# Sheet2.net
KiCad netlist of a schematic drawn in Altium Designer
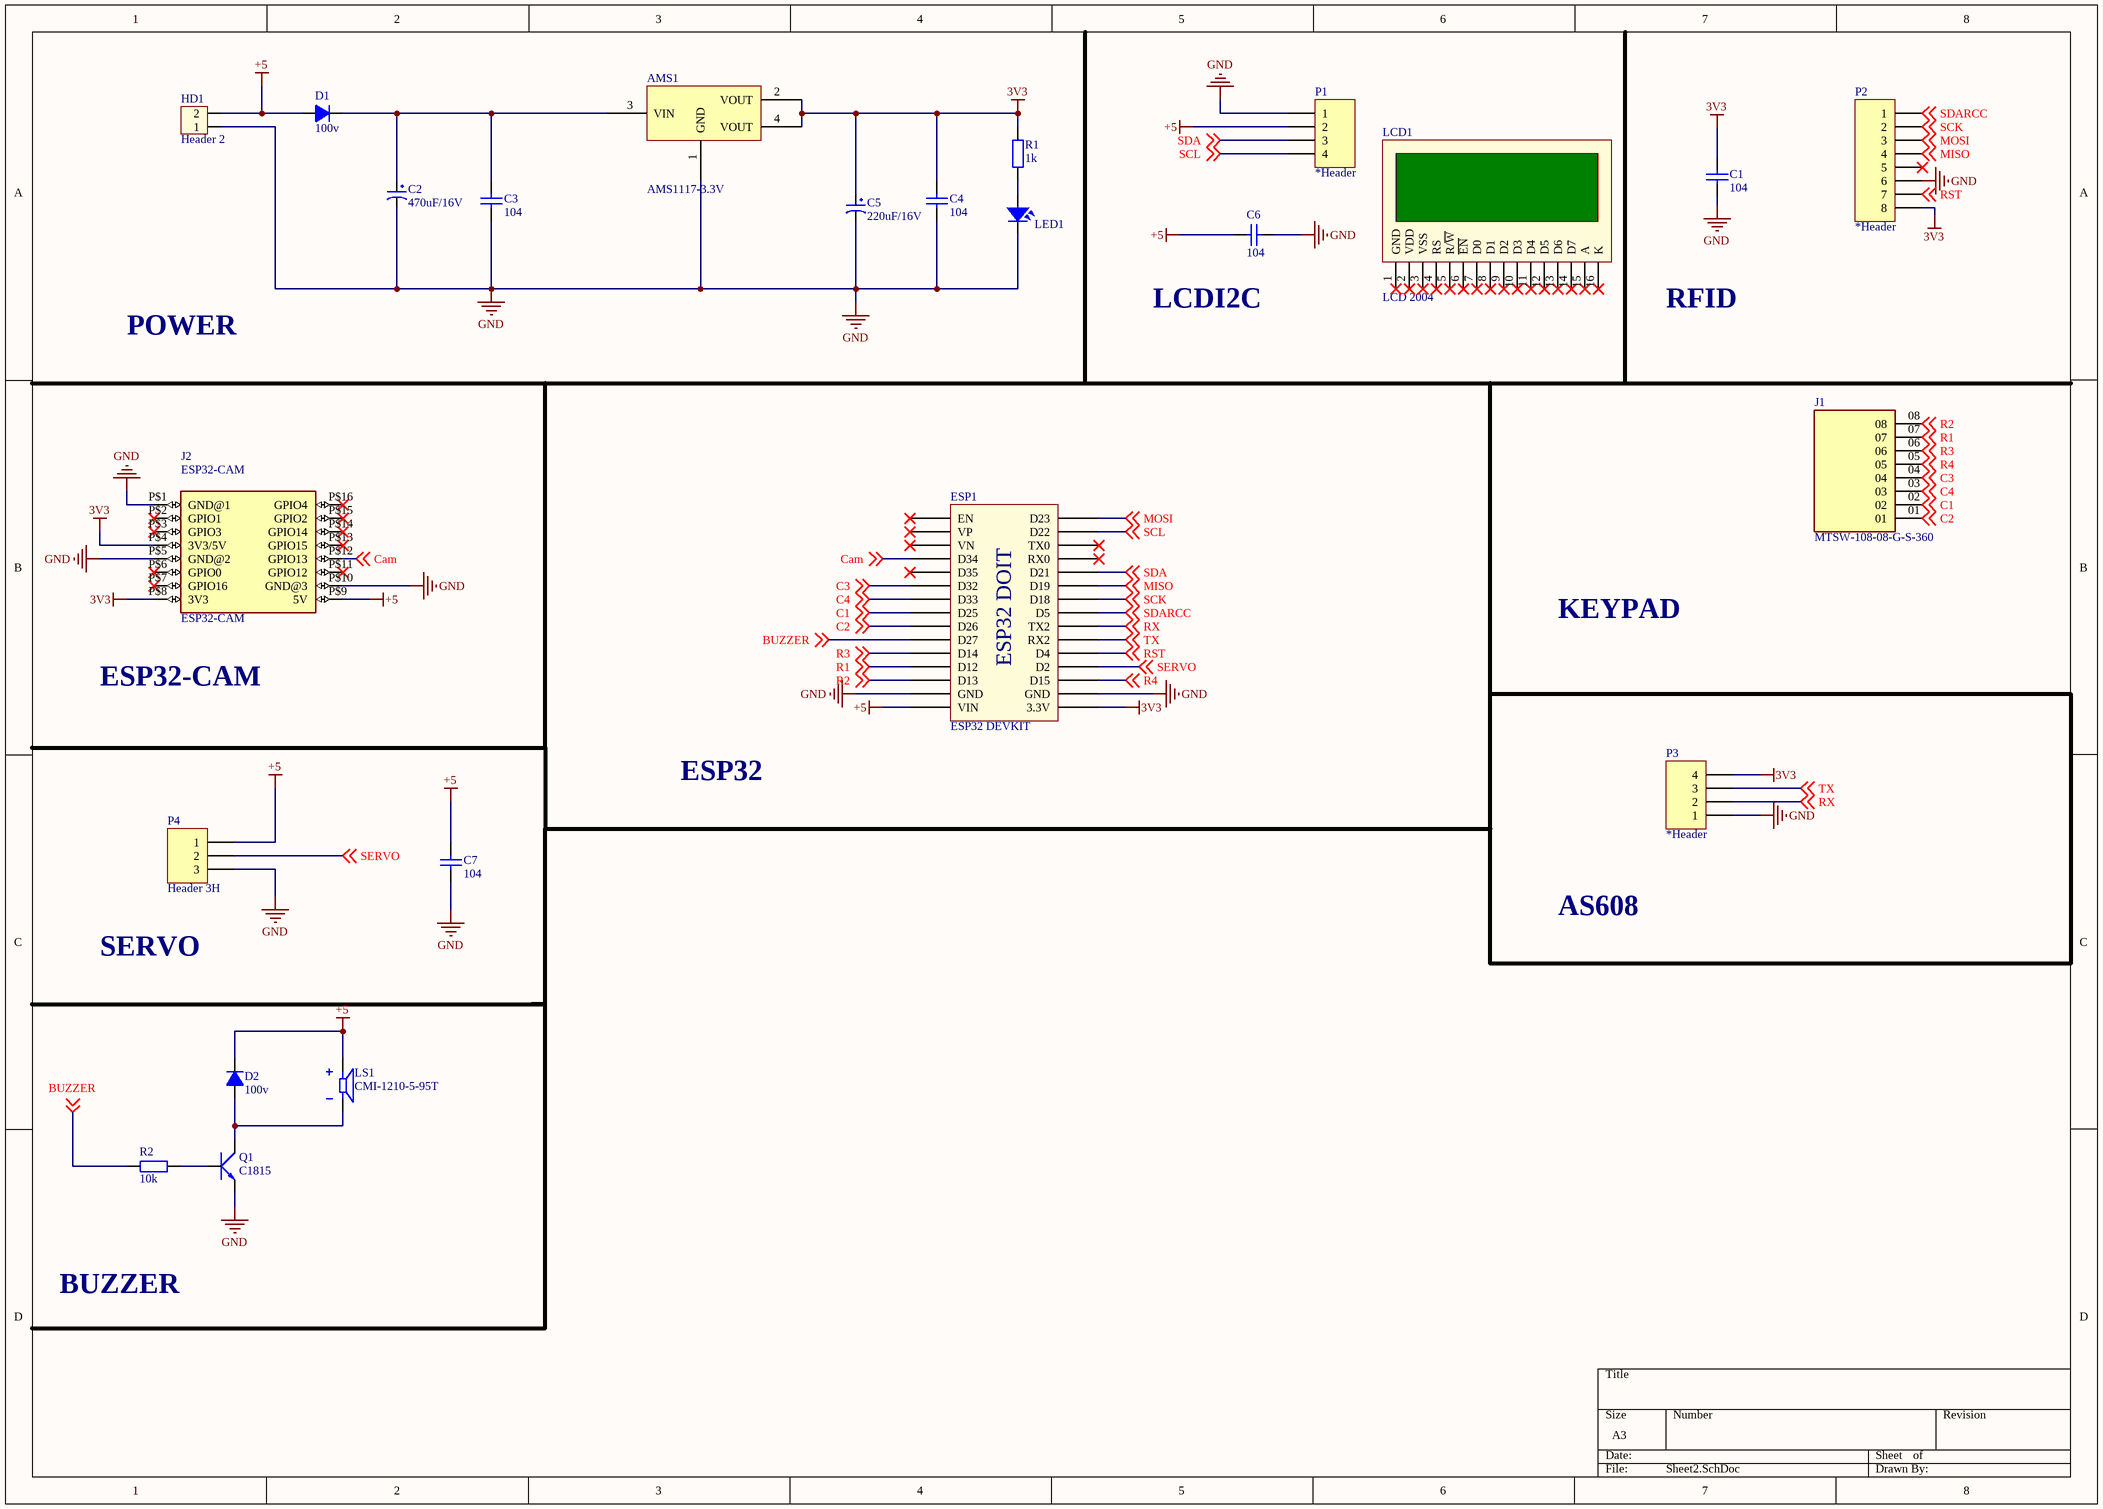
[diagram p0: Sheet2.SchDoc]

(export (version "E")
  (design (tool "Eeschema 10.0.6"))
  (components
    (comp (ref "AMS1")
      (value "AMS1117-3.3V")
      (footprint "SOT223")
      (description "Dán")
      (libsource (lib "Altium_Lib_by_KhueNguyenCreator") (part "AMS1117 SMD"))
    )
    (comp (ref "C1")
      (value "104")
      (footprint "tu gom")
      (description "Cắm")
      (libsource (lib "Altium_Lib_by_KhueNguyenCreator") (part "Tu gom 100 50V"))
    )
    (comp (ref "C2")
      (value "470uF/16V")
      (footprint "CP1/2")
      (description "Cap P  0,1uF < 22uF , 16 - 50V")
      (libsource (lib "VioletofSun") (part "CP1"))
    )
    (comp (ref "C3")
      (value "104")
      (footprint "tu gom")
      (description "Cắm")
      (libsource (lib "Altium_Lib_by_KhueNguyenCreator") (part "Tu gom 104 50V"))
    )
    (comp (ref "C4")
      (value "104")
      (footprint "tu gom")
      (description "Cắm")
      (libsource (lib "Altium_Lib_by_KhueNguyenCreator") (part "Tu gom 104 50V"))
    )
    (comp (ref "C5")
      (value "220uF/16V")
      (footprint "CP1/2")
      (description "Cap P  0,1uF < 22uF , 16 - 50V")
      (libsource (lib "VioletofSun") (part "CP1"))
    )
    (comp (ref "C6")
      (value "104")
      (footprint "tu gom")
      (description "Cắm")
      (libsource (lib "Altium_Lib_by_KhueNguyenCreator") (part "Tu gom 104 50V"))
    )
    (comp (ref "C7")
      (value "104")
      (footprint "tu gom")
      (description "Cắm")
      (libsource (lib "Altium_Lib_by_KhueNguyenCreator") (part "Tu gom 104 50V"))
    )
    (comp (ref "D1")
      (value "100v")
      (footprint "DIODE 1A")
      (description "Cắm")
      (libsource (lib "Altium_Lib_by_KhueNguyenCreator") (part "Diode 1N4007"))
    )
    (comp (ref "D2")
      (value "100v")
      (footprint "DIODE 1A")
      (description "Cắm")
      (libsource (lib "Altium_Lib_by_KhueNguyenCreator") (part "Diode 1N4007"))
    )
    (comp (ref "ESP1")
      (value "ESP32 DEVKIT")
      (footprint "ESP32 WROOM 32 KIT")
      (libsource (lib "Altium_Lib_by_KhueNguyenCreator") (part "ESP32 WROOM 32 KIT"))
    )
    (comp (ref "HD1")
      (value "Header 2")
      (footprint "HED2")
      (description "Header 2 (Green)")
      (libsource (lib "my Library") (part "Header 2"))
    )
    (comp (ref "J1")
      (value "MTSW-108-08-G-S-360")
      (footprint "SAMTEC_MTSW-108-08-G-S-360")
      (libsource (lib "MTSW-108-08-G-S-360") (part "MTSW-108-08-G-S-360"))
    )
    (comp (ref "J2")
      (value "ESP32-CAM")
      (footprint "ESP32-CAM")
      (fields (field (name "MF") "AI-Thinker"))
      (libsource (lib "ESP32-CAM") (part "ESP32-CAM"))
    )
    (comp (ref "LCD1")
      (value "LCD 2004")
      (footprint "LCD 2004")
      (description "LCD 2004 5V Xanh Dương")
      (libsource (lib "Altium_Lib_by_KhueNguyenCreator") (part "LCD 2004 5V"))
    )
    (comp (ref "LED1")
      (value "LED")
      (footprint "LED-5-RED")
      (description "LED Single colour Green and Red")
      (libsource (lib "LIBRARY") (part "LED"))
    )
    (comp (ref "LS1")
      (value "CMI-1210-5-95T")
      (footprint "XDCR_CMI-1210-5-95T")
      (description "12 mm, 5 Vdc, 98 dB, Through Hole, Magnetic Audio Indicator Buzzer")
      (fields (field (name "MF") "Same Sky"))
      (libsource (lib "CMI-1210-5-95T") (part "CMI-1210-5-95T"))
    )
    (comp (ref "P1")
      (value "*Header")
      (footprint "HDR1X4")
      (description "Header, 4-Pin, Right Angle")
      (fields (field (name "PUBLISHER") "Altium Limited"))
      (libsource (lib "") (part "Header 4_1"))
    )
    (comp (ref "P2")
      (value "*Header")
      (footprint "HDR1X8H")
      (description "Header, 8-Pin, Right Angle")
      (fields (field (name "PUBLISHER") "Altium Limited"))
      (libsource (lib "Cty1") (part "Header 8H"))
    )
    (comp (ref "P3")
      (value "*Header")
      (footprint "HDR1X4")
      (description "Header, 4-Pin, Right Angle")
      (fields (field (name "PUBLISHER") "Altium Limited"))
      (libsource (lib "Cty1") (part "Header 4"))
    )
    (comp (ref "P4")
      (value "Header 3H")
      (footprint "HDR1X3H")
      (description "Header, 3-Pin, Right Angle")
      (fields (field (name "PUBLISHER") "Altium Limited"))
      (libsource (lib "Devzone_SCHLib") (part "Header 3H"))
    )
    (comp (ref "Q1")
      (value "C1815")
      (footprint "TO92")
      (description "NPN transistor")
      (libsource (lib "Altium_Lib_by_KhueNguyenCreator") (part "C1815"))
    )
    (comp (ref "R1")
      (value "1k")
      (footprint "tro vach 1/4w")
      (description "Cắm")
      (libsource (lib "Altium_Lib_by_KhueNguyenCreator") (part "Tro Vach 1/4W 1% 1.2R"))
    )
    (comp (ref "R2")
      (value "10k")
      (footprint "tro vach 1/4w")
      (description "Căm")
      (libsource (lib "Altium_Lib_by_KhueNguyenCreator") (part "Tro Vach 1/4W 5% 10k"))
    )
  )
  (nets
    (net (code "1") (name "+5") (class "Default")
      (node (ref "C6") (pin "1") (pinfunction "1_1") (pintype "passive"))
      (node (ref "C7") (pin "1") (pinfunction "1_1") (pintype "passive"))
      (node (ref "D1") (pin "1") (pinfunction "A_1") (pintype "passive"))
      (node (ref "D2") (pin "2") (pinfunction "K_2") (pintype "passive"))
      (node (ref "ESP1") (pin "15") (pinfunction "VIN_15") (pintype "passive"))
      (node (ref "HD1") (pin "2") (pinfunction "2_2") (pintype "passive"))
      (node (ref "J2") (pin "P$9") (pinfunction "5V_P$9") (pintype "bidirectional"))
      (node (ref "LS1") (pin "P") (pinfunction "P_P") (pintype "passive"))
      (node (ref "P1") (pin "2") (pinfunction "2_2") (pintype "passive"))
      (node (ref "P4") (pin "1") (pinfunction "1_1") (pintype "passive"))
    )
    (net (code "2") (name "3V3") (class "Default")
      (node (ref "AMS1") (pin "2") (pinfunction "VOUT_2") (pintype "passive"))
      (node (ref "AMS1") (pin "4") (pinfunction "VOUT_4") (pintype "passive"))
      (node (ref "C1") (pin "1") (pinfunction "1_1") (pintype "passive"))
      (node (ref "C4") (pin "1") (pinfunction "1_1") (pintype "passive"))
      (node (ref "C5") (pin "1") (pinfunction "1_1") (pintype "passive"))
      (node (ref "ESP1") (pin "16") (pinfunction "3.3V_16") (pintype "passive"))
      (node (ref "J2") (pin "P$4") (pinfunction "3V3/5V_P$4") (pintype "bidirectional"))
      (node (ref "J2") (pin "P$8") (pinfunction "3V3_P$8") (pintype "bidirectional"))
      (node (ref "P2") (pin "8") (pinfunction "8_8") (pintype "passive"))
      (node (ref "P3") (pin "4") (pinfunction "4_4") (pintype "passive"))
      (node (ref "R1") (pin "2") (pinfunction "2_2") (pintype "passive"))
    )
    (net (code "3") (name "BUZZER") (class "Default")
      (node (ref "ESP1") (pin "10") (pinfunction "D27_10") (pintype "passive"))
      (node (ref "R2") (pin "1") (pinfunction "1_1") (pintype "passive"))
    )
    (net (code "4") (name "C1") (class "Default")
      (node (ref "ESP1") (pin "8") (pinfunction "D25_8") (pintype "passive"))
      (node (ref "J1") (pin "02") (pinfunction "02_02") (pintype "passive"))
    )
    (net (code "5") (name "C2") (class "Default")
      (node (ref "ESP1") (pin "9") (pinfunction "D26_9") (pintype "passive"))
      (node (ref "J1") (pin "01") (pinfunction "01_01") (pintype "passive"))
    )
    (net (code "6") (name "C3") (class "Default")
      (node (ref "ESP1") (pin "6") (pinfunction "D32_6") (pintype "passive"))
      (node (ref "J1") (pin "04") (pinfunction "04_04") (pintype "passive"))
    )
    (net (code "7") (name "C4") (class "Default")
      (node (ref "ESP1") (pin "7") (pinfunction "D33_7") (pintype "passive"))
      (node (ref "J1") (pin "03") (pinfunction "03_03") (pintype "passive"))
    )
    (net (code "8") (name "Cam") (class "Default")
      (node (ref "ESP1") (pin "4") (pinfunction "D34_4") (pintype "passive"))
      (node (ref "J2") (pin "P$12") (pinfunction "GPIO13_P$12") (pintype "bidirectional"))
    )
    (net (code "9") (name "GND") (class "Default")
      (node (ref "AMS1") (pin "1") (pinfunction "GND_1") (pintype "passive"))
      (node (ref "C1") (pin "2") (pinfunction "2_2") (pintype "passive"))
      (node (ref "C2") (pin "2") (pinfunction "2_2") (pintype "passive"))
      (node (ref "C3") (pin "2") (pinfunction "2_2") (pintype "passive"))
      (node (ref "C4") (pin "2") (pinfunction "2_2") (pintype "passive"))
      (node (ref "C5") (pin "2") (pinfunction "2_2") (pintype "passive"))
      (node (ref "C6") (pin "2") (pinfunction "2_2") (pintype "passive"))
      (node (ref "C7") (pin "2") (pinfunction "2_2") (pintype "passive"))
      (node (ref "ESP1") (pin "14") (pinfunction "GND_14") (pintype "passive"))
      (node (ref "ESP1") (pin "17") (pinfunction "GND_17") (pintype "passive"))
      (node (ref "HD1") (pin "1") (pinfunction "1_1") (pintype "passive"))
      (node (ref "J2") (pin "P$1") (pinfunction "GND@1_P$1") (pintype "bidirectional"))
      (node (ref "J2") (pin "P$10") (pinfunction "GND@3_P$10") (pintype "bidirectional"))
      (node (ref "J2") (pin "P$5") (pinfunction "GND@2_P$5") (pintype "bidirectional"))
      (node (ref "LED1") (pin "2") (pinfunction "2_2") (pintype "passive"))
      (node (ref "P1") (pin "1") (pinfunction "1_1") (pintype "passive"))
      (node (ref "P2") (pin "6") (pinfunction "6_6") (pintype "passive"))
      (node (ref "P3") (pin "1") (pinfunction "1_1") (pintype "passive"))
      (node (ref "P4") (pin "3") (pinfunction "3_3") (pintype "passive"))
      (node (ref "Q1") (pin "1") (pinfunction "E_1") (pintype "passive"))
    )
    (net (code "10") (name "MISO") (class "Default")
      (node (ref "ESP1") (pin "25") (pinfunction "D19_25") (pintype "passive"))
      (node (ref "P2") (pin "4") (pinfunction "4_4") (pintype "passive"))
    )
    (net (code "11") (name "MOSI") (class "Default")
      (node (ref "ESP1") (pin "30") (pinfunction "D23_30") (pintype "passive"))
      (node (ref "P2") (pin "3") (pinfunction "3_3") (pintype "passive"))
    )
    (net (code "12") (name "Net-(AMS1-VIN)") (class "Default")
      (node (ref "AMS1") (pin "3") (pinfunction "VIN_3") (pintype "passive"))
      (node (ref "C2") (pin "1") (pinfunction "1_1") (pintype "passive"))
      (node (ref "C3") (pin "1") (pinfunction "1_1") (pintype "passive"))
      (node (ref "D1") (pin "2") (pinfunction "K_2") (pintype "passive"))
    )
    (net (code "13") (name "Net-(D2-A)") (class "Default")
      (node (ref "D2") (pin "1") (pinfunction "A_1") (pintype "passive"))
      (node (ref "LS1") (pin "N") (pinfunction "N_N") (pintype "passive"))
      (node (ref "Q1") (pin "2") (pinfunction "C_2") (pintype "passive"))
    )
    (net (code "14") (name "Net-(LED1-Pad1)") (class "Default")
      (node (ref "LED1") (pin "1") (pinfunction "1_1") (pintype "passive"))
      (node (ref "R1") (pin "1") (pinfunction "1_1") (pintype "passive"))
    )
    (net (code "15") (name "Net-(Q1-B)") (class "Default")
      (node (ref "Q1") (pin "3") (pinfunction "B_3") (pintype "passive"))
      (node (ref "R2") (pin "2") (pinfunction "2_2") (pintype "passive"))
    )
    (net (code "16") (name "R1") (class "Default")
      (node (ref "ESP1") (pin "12") (pinfunction "D12_12") (pintype "passive"))
      (node (ref "J1") (pin "07") (pinfunction "07_07") (pintype "passive"))
    )
    (net (code "17") (name "R2") (class "Default")
      (node (ref "ESP1") (pin "13") (pinfunction "D13_13") (pintype "passive"))
      (node (ref "J1") (pin "08") (pinfunction "08_08") (pintype "passive"))
    )
    (net (code "18") (name "R3") (class "Default")
      (node (ref "ESP1") (pin "11") (pinfunction "D14_11") (pintype "passive"))
      (node (ref "J1") (pin "06") (pinfunction "06_06") (pintype "passive"))
    )
    (net (code "19") (name "R4") (class "Default")
      (node (ref "ESP1") (pin "18") (pinfunction "D15_18") (pintype "passive"))
      (node (ref "J1") (pin "05") (pinfunction "05_05") (pintype "passive"))
    )
    (net (code "20") (name "RST") (class "Default")
      (node (ref "ESP1") (pin "20") (pinfunction "D4_20") (pintype "passive"))
      (node (ref "P2") (pin "7") (pinfunction "7_7") (pintype "passive"))
    )
    (net (code "21") (name "RX") (class "Default")
      (node (ref "ESP1") (pin "22") (pinfunction "TX2_22") (pintype "passive"))
      (node (ref "P3") (pin "2") (pinfunction "2_2") (pintype "passive"))
    )
    (net (code "22") (name "SCK") (class "Default")
      (node (ref "ESP1") (pin "24") (pinfunction "D18_24") (pintype "passive"))
      (node (ref "P2") (pin "2") (pinfunction "2_2") (pintype "passive"))
    )
    (net (code "23") (name "SCL") (class "Default")
      (node (ref "ESP1") (pin "29") (pinfunction "D22_29") (pintype "passive"))
      (node (ref "P1") (pin "4") (pinfunction "4_4") (pintype "passive"))
    )
    (net (code "24") (name "SDA") (class "Default")
      (node (ref "ESP1") (pin "26") (pinfunction "D21_26") (pintype "passive"))
      (node (ref "P1") (pin "3") (pinfunction "3_3") (pintype "passive"))
    )
    (net (code "25") (name "SDARCC") (class "Default")
      (node (ref "ESP1") (pin "23") (pinfunction "D5_23") (pintype "passive"))
      (node (ref "P2") (pin "1") (pinfunction "1_1") (pintype "passive"))
    )
    (net (code "26") (name "SERVO") (class "Default")
      (node (ref "ESP1") (pin "19") (pinfunction "D2_19") (pintype "passive"))
      (node (ref "P4") (pin "2") (pinfunction "2_2") (pintype "passive"))
    )
    (net (code "27") (name "TX") (class "Default")
      (node (ref "ESP1") (pin "21") (pinfunction "RX2_21") (pintype "passive"))
      (node (ref "P3") (pin "3") (pinfunction "3_3") (pintype "passive"))
    )
    (net (code "28") (name "unconnected-(ESP1-D35-Pad5)") (class "Default")
      (node (ref "ESP1") (pin "5") (pinfunction "D35_5") (pintype "passive+no_connect"))
    )
    (net (code "29") (name "unconnected-(ESP1-EN-Pad1)") (class "Default")
      (node (ref "ESP1") (pin "1") (pinfunction "EN_1") (pintype "passive+no_connect"))
    )
    (net (code "30") (name "unconnected-(ESP1-RX0-Pad27)") (class "Default")
      (node (ref "ESP1") (pin "27") (pinfunction "RX0_27") (pintype "passive+no_connect"))
    )
    (net (code "31") (name "unconnected-(ESP1-TX0-Pad28)") (class "Default")
      (node (ref "ESP1") (pin "28") (pinfunction "TX0_28") (pintype "passive+no_connect"))
    )
    (net (code "32") (name "unconnected-(ESP1-VN-Pad3)") (class "Default")
      (node (ref "ESP1") (pin "3") (pinfunction "VN_3") (pintype "passive+no_connect"))
    )
    (net (code "33") (name "unconnected-(ESP1-VP-Pad2)") (class "Default")
      (node (ref "ESP1") (pin "2") (pinfunction "VP_2") (pintype "passive+no_connect"))
    )
    (net (code "34") (name "unconnected-(J2-GPIO0-PadP$6)") (class "Default")
      (node (ref "J2") (pin "P$6") (pinfunction "GPIO0_P$6") (pintype "bidirectional+no_connect"))
    )
    (net (code "35") (name "unconnected-(J2-GPIO1-PadP$2)") (class "Default")
      (node (ref "J2") (pin "P$2") (pinfunction "GPIO1_P$2") (pintype "bidirectional+no_connect"))
    )
    (net (code "36") (name "unconnected-(J2-GPIO2-PadP$15)") (class "Default")
      (node (ref "J2") (pin "P$15") (pinfunction "GPIO2_P$15") (pintype "bidirectional+no_connect"))
    )
    (net (code "37") (name "unconnected-(J2-GPIO3-PadP$3)") (class "Default")
      (node (ref "J2") (pin "P$3") (pinfunction "GPIO3_P$3") (pintype "bidirectional+no_connect"))
    )
    (net (code "38") (name "unconnected-(J2-GPIO4-PadP$16)") (class "Default")
      (node (ref "J2") (pin "P$16") (pinfunction "GPIO4_P$16") (pintype "bidirectional+no_connect"))
    )
    (net (code "39") (name "unconnected-(J2-GPIO12-PadP$11)") (class "Default")
      (node (ref "J2") (pin "P$11") (pinfunction "GPIO12_P$11") (pintype "bidirectional+no_connect"))
    )
    (net (code "40") (name "unconnected-(J2-GPIO14-PadP$14)") (class "Default")
      (node (ref "J2") (pin "P$14") (pinfunction "GPIO14_P$14") (pintype "bidirectional+no_connect"))
    )
    (net (code "41") (name "unconnected-(J2-GPIO15-PadP$13)") (class "Default")
      (node (ref "J2") (pin "P$13") (pinfunction "GPIO15_P$13") (pintype "bidirectional+no_connect"))
    )
    (net (code "42") (name "unconnected-(J2-GPIO16-PadP$7)") (class "Default")
      (node (ref "J2") (pin "P$7") (pinfunction "GPIO16_P$7") (pintype "bidirectional+no_connect"))
    )
    (net (code "43") (name "unconnected-(LCD1-A-Pad15)") (class "Default")
      (node (ref "LCD1") (pin "15") (pinfunction "A_15") (pintype "passive+no_connect"))
    )
    (net (code "44") (name "unconnected-(LCD1-D0-Pad7)") (class "Default")
      (node (ref "LCD1") (pin "7") (pinfunction "D0_7") (pintype "passive+no_connect"))
    )
    (net (code "45") (name "unconnected-(LCD1-D1-Pad8)") (class "Default")
      (node (ref "LCD1") (pin "8") (pinfunction "D1_8") (pintype "passive+no_connect"))
    )
    (net (code "46") (name "unconnected-(LCD1-D2-Pad9)") (class "Default")
      (node (ref "LCD1") (pin "9") (pinfunction "D2_9") (pintype "passive+no_connect"))
    )
    (net (code "47") (name "unconnected-(LCD1-D3-Pad10)") (class "Default")
      (node (ref "LCD1") (pin "10") (pinfunction "D3_10") (pintype "passive+no_connect"))
    )
    (net (code "48") (name "unconnected-(LCD1-D4-Pad11)") (class "Default")
      (node (ref "LCD1") (pin "11") (pinfunction "D4_11") (pintype "passive+no_connect"))
    )
    (net (code "49") (name "unconnected-(LCD1-D5-Pad12)") (class "Default")
      (node (ref "LCD1") (pin "12") (pinfunction "D5_12") (pintype "passive+no_connect"))
    )
    (net (code "50") (name "unconnected-(LCD1-D6-Pad13)") (class "Default")
      (node (ref "LCD1") (pin "13") (pinfunction "D6_13") (pintype "passive+no_connect"))
    )
    (net (code "51") (name "unconnected-(LCD1-D7-Pad14)") (class "Default")
      (node (ref "LCD1") (pin "14") (pinfunction "D7_14") (pintype "passive+no_connect"))
    )
    (net (code "52") (name "unconnected-(LCD1-GND-Pad1)") (class "Default")
      (node (ref "LCD1") (pin "1") (pinfunction "GND_1") (pintype "passive+no_connect"))
    )
    (net (code "53") (name "unconnected-(LCD1-K-Pad16)") (class "Default")
      (node (ref "LCD1") (pin "16") (pinfunction "K_16") (pintype "passive+no_connect"))
    )
    (net (code "54") (name "unconnected-(LCD1-RS-Pad4)") (class "Default")
      (node (ref "LCD1") (pin "4") (pinfunction "RS_4") (pintype "passive+no_connect"))
    )
    (net (code "55") (name "unconnected-(LCD1-R{slash}~{W}-Pad5)") (class "Default")
      (node (ref "LCD1") (pin "5") (pinfunction "R/~{W}_5") (pintype "passive+no_connect"))
    )
    (net (code "56") (name "unconnected-(LCD1-VDD-Pad2)") (class "Default")
      (node (ref "LCD1") (pin "2") (pinfunction "VDD_2") (pintype "passive+no_connect"))
    )
    (net (code "57") (name "unconnected-(LCD1-VSS-Pad3)") (class "Default")
      (node (ref "LCD1") (pin "3") (pinfunction "VSS_3") (pintype "passive+no_connect"))
    )
    (net (code "58") (name "unconnected-(LCD1-~{EN}-Pad6)") (class "Default")
      (node (ref "LCD1") (pin "6") (pinfunction "~{EN}_6") (pintype "passive+no_connect"))
    )
    (net (code "59") (name "unconnected-(P2-Pad5)") (class "Default")
      (node (ref "P2") (pin "5") (pinfunction "5_5") (pintype "passive+no_connect"))
    )
  )
)
